# Bluetooth_RC_car.net
KiCad netlist of a schematic drawn in EAGLE
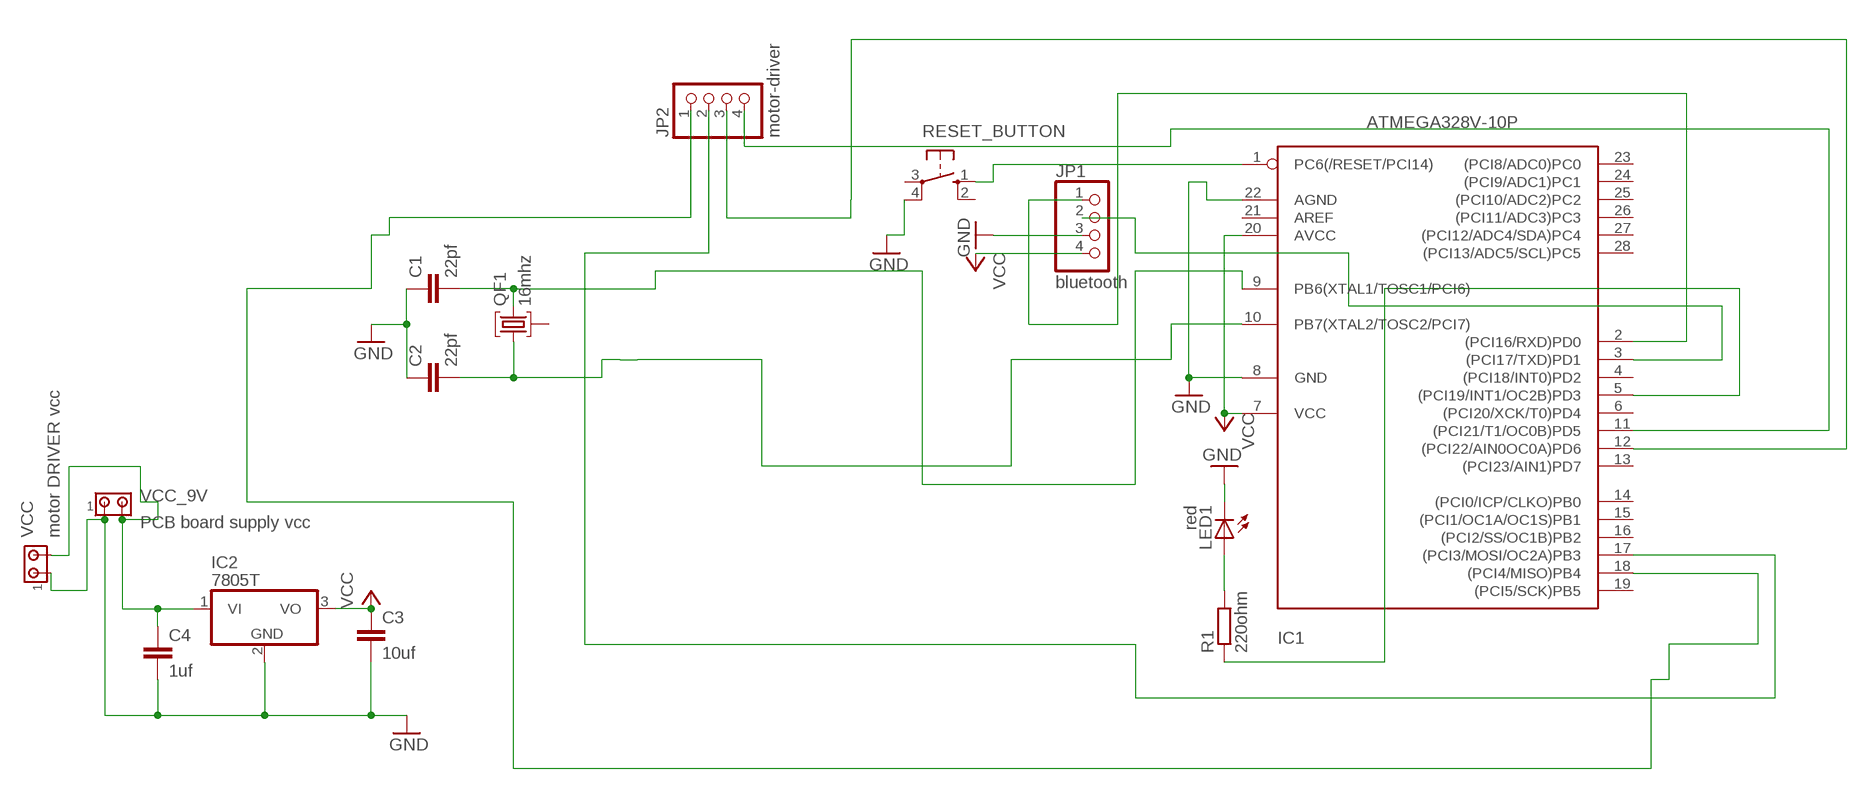
[diagram p0: schematic, sheet 1]

(export (version "E")
  (design (tool "Eeschema 10.0.6"))
  (components
    (comp (ref "C1")
      (value "22pf")
      (footprint "eagle-import:C5B2.5")
      (libsource (lib "eagle-import") (part "C5/2.5"))
    )
    (comp (ref "C2")
      (value "22pf")
      (footprint "eagle-import:C5B2.5")
      (libsource (lib "eagle-import") (part "C5/2.5"))
    )
    (comp (ref "C3")
      (value "10uf")
      (footprint "eagle-import:C5B3")
      (libsource (lib "eagle-import") (part "C5/3"))
    )
    (comp (ref "C4")
      (value "1uf")
      (footprint "eagle-import:C5B3")
      (libsource (lib "eagle-import") (part "C5/3"))
    )
    (comp (ref "IC1")
      (value "ATMEGA328V-10P")
      (footprint "eagle-import:DIL28-3")
      (libsource (lib "eagle-import") (part "ATMEGA328PV-10"))
    )
    (comp (ref "IC2")
      (value "7805T")
      (footprint "eagle-import:TO220H")
      (libsource (lib "eagle-import") (part "78T05"))
    )
    (comp (ref "JP1")
      (value "bluetooth")
      (footprint "eagle-import:1X04")
      (libsource (lib "eagle-import") (part "PINHD-1X4"))
    )
    (comp (ref "JP2")
      (value "motor-driver")
      (footprint "eagle-import:1X04")
      (libsource (lib "eagle-import") (part "PINHD-1X4"))
    )
    (comp (ref "LED1")
      (value "red")
      (footprint "eagle-import:LED5MM")
      (libsource (lib "eagle-import") (part "LED5MM"))
    )
    (comp (ref "QF1")
      (value "16mhz")
      (footprint "eagle-import:UM1")
      (libsource (lib "eagle-import") (part "17M15AUM1"))
    )
    (comp (ref "R1")
      (value "220ohm")
      (footprint "eagle-import:0207_7")
      (libsource (lib "eagle-import") (part "R-EU_0207/7"))
    )
    (comp (ref "RESET_BUTTON")
      (value "40-XX")
      (footprint "eagle-import:B3F-40XX")
      (fields (field (name "MF") "OMRON COMPONENTS USA") (field (name "MPN") "B3F-4000"))
      (libsource (lib "eagle-import") (part "40-XX"))
    )
    (comp (ref "VCC")
      (value "motor DRIVER vcc")
      (footprint "eagle-import:10X02MTA")
      (libsource (lib "eagle-import") (part "MTA02-100"))
    )
    (comp (ref "VCC_9V")
      (value "PCB board supply vcc")
      (footprint "eagle-import:10X02MTA")
      (libsource (lib "eagle-import") (part "MTA02-100"))
    )
  )
  (nets
    (net (code "1") (name "GND") (class "Default")
      (node (ref "C1") (pin "1") (pinfunction "1_1") (pintype "passive"))
      (node (ref "C2") (pin "1") (pinfunction "1_1") (pintype "passive"))
      (node (ref "C3") (pin "2") (pinfunction "2_2") (pintype "passive"))
      (node (ref "C4") (pin "2") (pinfunction "2_2") (pintype "passive"))
      (node (ref "IC1") (pin "22") (pinfunction "AGND_22") (pintype "bidirectional"))
      (node (ref "IC1") (pin "8") (pinfunction "GND_8") (pintype "bidirectional"))
      (node (ref "IC2") (pin "2") (pinfunction "GND_2") (pintype "passive"))
      (node (ref "JP1") (pin "3") (pinfunction "3_3") (pintype "passive"))
      (node (ref "LED1") (pin "K") (pinfunction "C_K") (pintype "passive"))
      (node (ref "RESET_BUTTON") (pin "4") (pinfunction "P1_4") (pintype "passive"))
      (node (ref "VCC") (pin "1") (pinfunction "1_1") (pintype "passive"))
      (node (ref "VCC_9V") (pin "1") (pinfunction "1_1") (pintype "passive"))
    )
    (net (code "2") (name "Net-(IC1-(PCI3{slash}MOSI{slash}OC2A)PB3)") (class "Default")
      (node (ref "IC1") (pin "17") (pinfunction "(PCI3/MOSI/OC2A)PB3_17") (pintype "bidirectional"))
      (node (ref "JP2") (pin "2") (pinfunction "2_2") (pintype "passive"))
    )
    (net (code "3") (name "Net-(IC1-(PCI4{slash}MISO)PB4)") (class "Default")
      (node (ref "IC1") (pin "18") (pinfunction "(PCI4/MISO)PB4_18") (pintype "bidirectional"))
      (node (ref "JP2") (pin "1") (pinfunction "1_1") (pintype "passive"))
    )
    (net (code "4") (name "Net-(IC1-(PCI16{slash}RXD)PD0)") (class "Default")
      (node (ref "IC1") (pin "2") (pinfunction "(PCI16/RXD)PD0_2") (pintype "bidirectional"))
      (node (ref "JP1") (pin "1") (pinfunction "1_1") (pintype "passive"))
    )
    (net (code "5") (name "Net-(IC1-(PCI17{slash}TXD)PD1)") (class "Default")
      (node (ref "IC1") (pin "3") (pinfunction "(PCI17/TXD)PD1_3") (pintype "bidirectional"))
      (node (ref "JP1") (pin "2") (pinfunction "2_2") (pintype "passive"))
    )
    (net (code "6") (name "Net-(IC1-(PCI19{slash}INT1{slash}OC2B)PD3)") (class "Default")
      (node (ref "IC1") (pin "5") (pinfunction "(PCI19/INT1/OC2B)PD3_5") (pintype "bidirectional"))
      (node (ref "R1") (pin "1") (pinfunction "1_1") (pintype "passive"))
    )
    (net (code "7") (name "Net-(IC1-(PCI21{slash}T1{slash}OC0B)PD5)") (class "Default")
      (node (ref "IC1") (pin "11") (pinfunction "(PCI21/T1/OC0B)PD5_11") (pintype "bidirectional"))
      (node (ref "JP2") (pin "4") (pinfunction "4_4") (pintype "passive"))
    )
    (net (code "8") (name "Net-(IC1-(PCI22{slash}AIN0OC0A)PD6)") (class "Default")
      (node (ref "IC1") (pin "12") (pinfunction "(PCI22/AIN0OC0A)PD6_12") (pintype "bidirectional"))
      (node (ref "JP2") (pin "3") (pinfunction "3_3") (pintype "passive"))
    )
    (net (code "9") (name "Net-(IC1-PB6(XTAL1{slash}TOSC1{slash}PCI6))") (class "Default")
      (node (ref "C1") (pin "2") (pinfunction "2_2") (pintype "passive"))
      (node (ref "IC1") (pin "9") (pinfunction "PB6(XTAL1/TOSC1/PCI6)_9") (pintype "bidirectional"))
      (node (ref "QF1") (pin "3") (pinfunction "3_3") (pintype "passive"))
    )
    (net (code "10") (name "Net-(IC1-PB7(XTAL2{slash}TOSC2{slash}PCI7))") (class "Default")
      (node (ref "C2") (pin "2") (pinfunction "2_2") (pintype "passive"))
      (node (ref "IC1") (pin "10") (pinfunction "PB7(XTAL2/TOSC2/PCI7)_10") (pintype "bidirectional"))
      (node (ref "QF1") (pin "1") (pinfunction "1_1") (pintype "passive"))
    )
    (net (code "11") (name "Net-(IC1-PC6({slash}RESET{slash}PCI14))") (class "Default")
      (node (ref "IC1") (pin "1") (pinfunction "PC6(/RESET/PCI14)_1") (pintype "bidirectional"))
      (node (ref "RESET_BUTTON") (pin "1") (pinfunction "S_1") (pintype "passive"))
    )
    (net (code "12") (name "Net-(IC2-VI)") (class "Default")
      (node (ref "C4") (pin "1") (pinfunction "1_1") (pintype "passive"))
      (node (ref "IC2") (pin "1") (pinfunction "VI_1") (pintype "input"))
      (node (ref "VCC") (pin "2") (pinfunction "2_2") (pintype "passive"))
      (node (ref "VCC_9V") (pin "2") (pinfunction "2_2") (pintype "passive"))
    )
    (net (code "13") (name "Net-(LED1-PadA)") (class "Default")
      (node (ref "LED1") (pin "A") (pinfunction "A_A") (pintype "passive"))
      (node (ref "R1") (pin "2") (pinfunction "2_2") (pintype "passive"))
    )
    (net (code "14") (name "VCC") (class "Default")
      (node (ref "C3") (pin "1") (pinfunction "1_1") (pintype "passive"))
      (node (ref "IC1") (pin "20") (pinfunction "AVCC_20") (pintype "bidirectional"))
      (node (ref "IC1") (pin "7") (pinfunction "VCC_7") (pintype "bidirectional"))
      (node (ref "IC2") (pin "3") (pinfunction "VO_3") (pintype "passive"))
      (node (ref "JP1") (pin "4") (pinfunction "4_4") (pintype "passive"))
    )
    (net (code "15") (name "unconnected-(IC1-(PCI0{slash}ICP{slash}CLKO)PB0-Pad14)") (class "Default")
      (node (ref "IC1") (pin "14") (pinfunction "(PCI0/ICP/CLKO)PB0_14") (pintype "bidirectional"))
    )
    (net (code "16") (name "unconnected-(IC1-(PCI1{slash}OC1A{slash}OC1S)PB1-Pad15)") (class "Default")
      (node (ref "IC1") (pin "15") (pinfunction "(PCI1/OC1A/OC1S)PB1_15") (pintype "bidirectional"))
    )
    (net (code "17") (name "unconnected-(IC1-(PCI2{slash}SS{slash}OC1B)PB2-Pad16)") (class "Default")
      (node (ref "IC1") (pin "16") (pinfunction "(PCI2/SS/OC1B)PB2_16") (pintype "bidirectional"))
    )
    (net (code "18") (name "unconnected-(IC1-(PCI5{slash}SCK)PB5-Pad19)") (class "Default")
      (node (ref "IC1") (pin "19") (pinfunction "(PCI5/SCK)PB5_19") (pintype "bidirectional"))
    )
    (net (code "19") (name "unconnected-(IC1-(PCI8{slash}ADC0)PC0-Pad23)") (class "Default")
      (node (ref "IC1") (pin "23") (pinfunction "(PCI8/ADC0)PC0_23") (pintype "bidirectional"))
    )
    (net (code "20") (name "unconnected-(IC1-(PCI9{slash}ADC1)PC1-Pad24)") (class "Default")
      (node (ref "IC1") (pin "24") (pinfunction "(PCI9/ADC1)PC1_24") (pintype "bidirectional"))
    )
    (net (code "21") (name "unconnected-(IC1-(PCI10{slash}ADC2)PC2-Pad25)") (class "Default")
      (node (ref "IC1") (pin "25") (pinfunction "(PCI10/ADC2)PC2_25") (pintype "bidirectional"))
    )
    (net (code "22") (name "unconnected-(IC1-(PCI11{slash}ADC3)PC3-Pad26)") (class "Default")
      (node (ref "IC1") (pin "26") (pinfunction "(PCI11/ADC3)PC3_26") (pintype "bidirectional"))
    )
    (net (code "23") (name "unconnected-(IC1-(PCI12{slash}ADC4{slash}SDA)PC4-Pad27)") (class "Default")
      (node (ref "IC1") (pin "27") (pinfunction "(PCI12/ADC4/SDA)PC4_27") (pintype "bidirectional"))
    )
    (net (code "24") (name "unconnected-(IC1-(PCI13{slash}ADC5{slash}SCL)PC5-Pad28)") (class "Default")
      (node (ref "IC1") (pin "28") (pinfunction "(PCI13/ADC5/SCL)PC5_28") (pintype "bidirectional"))
    )
    (net (code "25") (name "unconnected-(IC1-(PCI18{slash}INT0)PD2-Pad4)") (class "Default")
      (node (ref "IC1") (pin "4") (pinfunction "(PCI18/INT0)PD2_4") (pintype "bidirectional"))
    )
    (net (code "26") (name "unconnected-(IC1-(PCI20{slash}XCK{slash}T0)PD4-Pad6)") (class "Default")
      (node (ref "IC1") (pin "6") (pinfunction "(PCI20/XCK/T0)PD4_6") (pintype "bidirectional"))
    )
    (net (code "27") (name "unconnected-(IC1-(PCI23{slash}AIN1)PD7-Pad13)") (class "Default")
      (node (ref "IC1") (pin "13") (pinfunction "(PCI23/AIN1)PD7_13") (pintype "bidirectional"))
    )
    (net (code "28") (name "unconnected-(IC1-AREF-Pad21)") (class "Default")
      (node (ref "IC1") (pin "21") (pinfunction "AREF_21") (pintype "bidirectional"))
    )
    (net (code "29") (name "unconnected-(QF1-Pad2)") (class "Default")
      (node (ref "QF1") (pin "2") (pinfunction "2_2") (pintype "passive"))
    )
    (net (code "30") (name "unconnected-(RESET_BUTTON-P-Pad3)") (class "Default")
      (node (ref "RESET_BUTTON") (pin "3") (pinfunction "P_3") (pintype "passive"))
    )
    (net (code "31") (name "unconnected-(RESET_BUTTON-S1-Pad2)") (class "Default")
      (node (ref "RESET_BUTTON") (pin "2") (pinfunction "S1_2") (pintype "passive"))
    )
  )
)
